# Titan_Balancer_1.net
KiCad netlist of a schematic drawn in Altium Designer
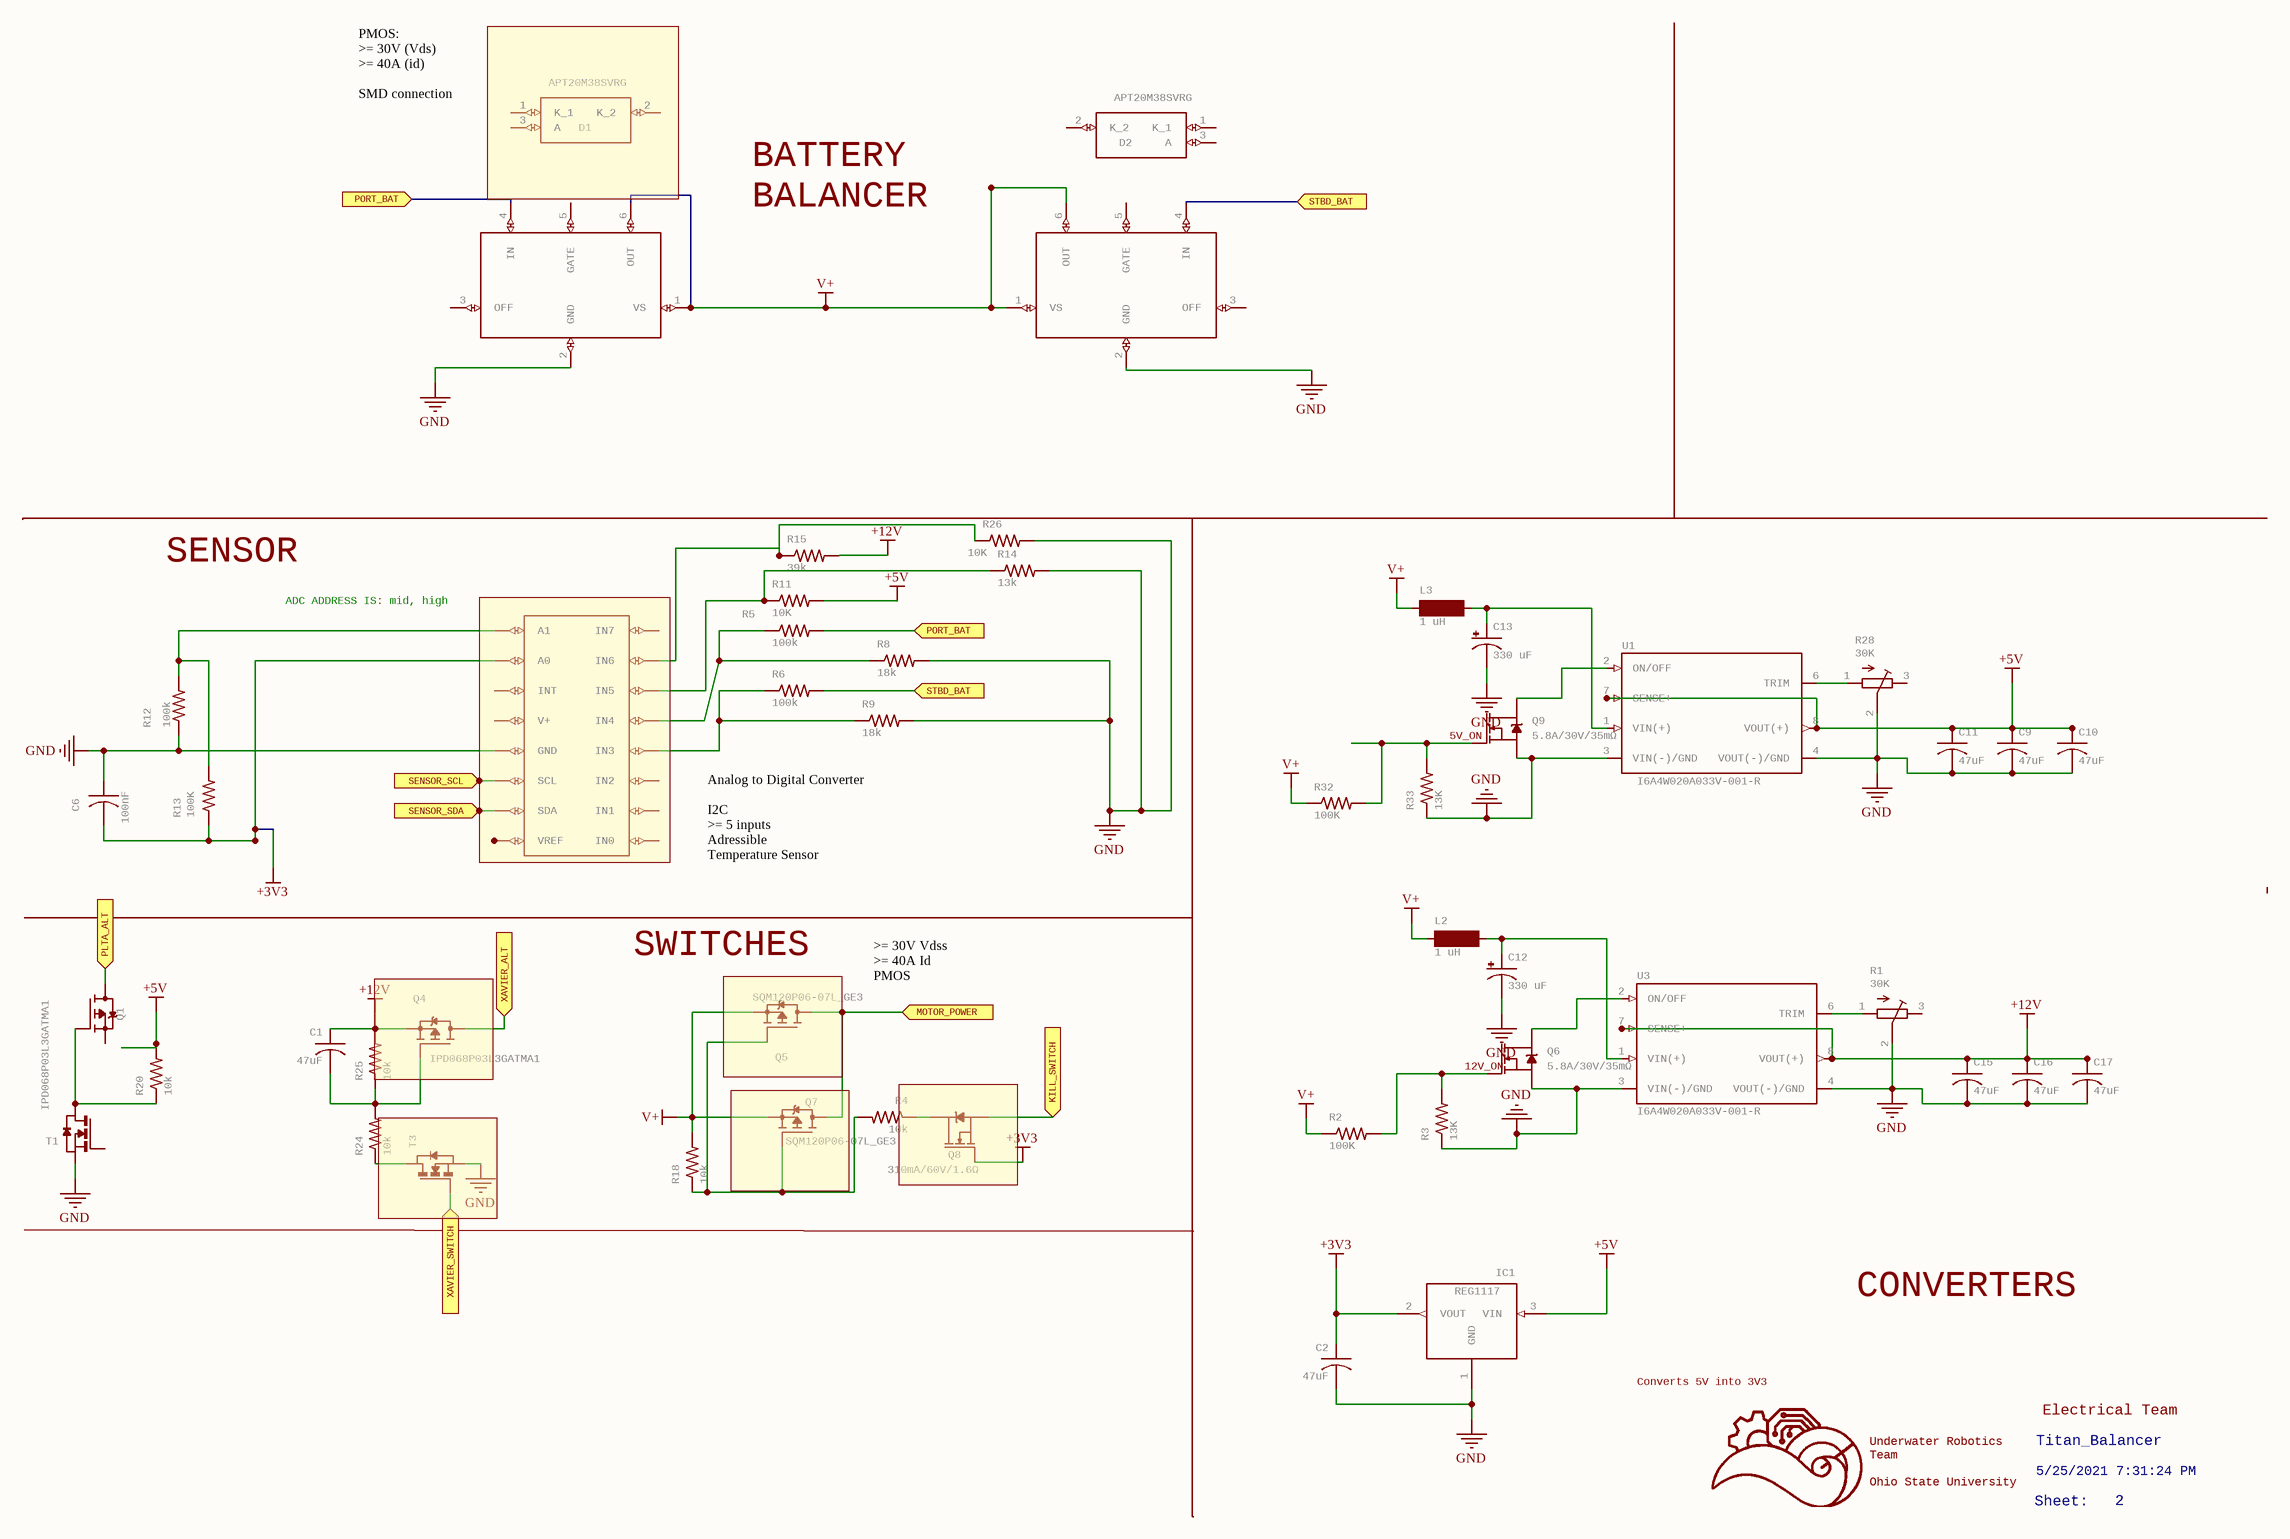
[diagram p0: Titan_Balancer_1.SchDoc]

(export (version "E")
  (design (tool "Eeschema 10.0.6"))
  (components
    (comp (ref "C1")
      (value "47uF")
      (footprint "C0603")
      (description "CAPACITOR, American symbol")
      (libsource (lib "rcl") (part "C-USC0603"))
    )
    (comp (ref "C2")
      (value "47uF")
      (footprint "C0603")
      (description "CAPACITOR, American symbol")
      (libsource (lib "") (part "C-USC0603_1"))
    )
    (comp (ref "C6")
      (value "100nF")
      (footprint "C0603")
      (description "CAPACITOR, American symbol")
      (libsource (lib "rcl") (part "C-USC0603"))
    )
    (comp (ref "C9")
      (value "47uF")
      (footprint "C0603")
      (description "CAPACITOR, American symbol")
      (libsource (lib "rcl") (part "C-USC0603"))
    )
    (comp (ref "C10")
      (value "47uF")
      (footprint "C0603")
      (description "CAPACITOR, American symbol")
      (libsource (lib "rcl") (part "C-USC0603"))
    )
    (comp (ref "C11")
      (value "47uF")
      (footprint "C0603")
      (description "CAPACITOR, American symbol")
      (libsource (lib "rcl") (part "C-USC0603"))
    )
    (comp (ref "C12")
      (value "330 uF")
      (footprint "153CLV-0810")
      (description "POLARIZED CAPACITOR, American symbol")
      (libsource (lib "rcl") (part "CPOL-US153CLV-0810"))
    )
    (comp (ref "C13")
      (value "330 uF")
      (footprint "153CLV-0810")
      (description "POLARIZED CAPACITOR, American symbol")
      (libsource (lib "rcl") (part "CPOL-US153CLV-0810"))
    )
    (comp (ref "C15")
      (value "47uF")
      (footprint "C0603")
      (description "CAPACITOR, American symbol")
      (libsource (lib "rcl") (part "C-USC0603"))
    )
    (comp (ref "C16")
      (value "47uF")
      (footprint "C0603")
      (description "CAPACITOR, American symbol")
      (libsource (lib "rcl") (part "C-USC0603"))
    )
    (comp (ref "C17")
      (value "47uF")
      (footprint "C0603")
      (description "CAPACITOR, American symbol")
      (libsource (lib "rcl") (part "C-USC0603"))
    )
    (comp (ref "D1")
      (value "APT20M38SVRG")
      (footprint "APT60DQ60SG")
      (description "Rectifiers FG, FRED, 600V, 60A, D3, TO-268, RoHS   Source:  Datasheet")
      (fields
        (field (name "ARROW_PART_NUMBER") "APT60DQ60SG")
        (field (name "MOUSER_PART_NUMBER") "494-APT60DQ60SG")
      )
      (libsource (lib "APT60DQ60SG") (part "APT60DQ60SG"))
    )
    (comp (ref "D2")
      (value "APT20M38SVRG")
      (footprint "APT60DQ60SG")
      (description "Rectifiers FG, FRED, 600V, 60A, D3, TO-268, RoHS   Source:  Datasheet")
      (fields
        (field (name "ARROW_PART_NUMBER") "APT60DQ60SG")
        (field (name "MOUSER_PART_NUMBER") "494-APT60DQ60SG")
      )
      (libsource (lib "APT60DQ60SG") (part "APT60DQ60SG"))
    )
    (comp (ref "IC1")
      (value "REG1117")
      (footprint "SOT223")
      (description "800mA and 1A Low Dropout (LDO) Positive Regulator   1.8V, 2.5V, 2.85V, 3.3V, 5V, and Adj")
      (fields (field (name "MF") "MF") (field (name "LIBRARYNAME") "burr-brown"))
      (libsource (lib "burr-brown") (part "REG1117"))
    )
    (comp (ref "L2")
      (value "1 uH")
      (footprint "MS85")
      (description "INDUCTOR   SMD power inductor")
      (fields
        (field (name "MF") "MF")
        (field (name "MPN") "MPN")
        (field (name "LIBRARYNAME") "inductor-neosid")
      )
      (libsource (lib "inductor-neosid") (part "MS85"))
    )
    (comp (ref "L3")
      (value "1 uH")
      (footprint "MS85")
      (description "INDUCTOR   SMD power inductor")
      (fields
        (field (name "MF") "MF")
        (field (name "MPN") "MPN")
        (field (name "LIBRARYNAME") "inductor-neosid")
      )
      (libsource (lib "inductor-neosid") (part "MS85"))
    )
    (comp (ref "Q1")
      (value "IPD068P03L3GATMA1")
      (footprint "TO252")
      (libsource (lib "transistor-fet") (part "SPD30P06PTO252"))
    )
    (comp (ref "Q4")
      (value "IPD068P03L3GATMA1")
      (footprint "TO252")
      (libsource (lib "transistor-fet") (part "SPD30P06PTO252"))
    )
    (comp (ref "Q5")
      (value "SQM120P06-07L_GE3")
      (footprint "TO263")
      (libsource (lib "transistor-fet") (part "SPB80P06P"))
    )
    (comp (ref "Q6")
      (value "5.8A/30V/35mΩ")
      (footprint "SOT23-3")
      (libsource (lib "SparkFun-DiscreteSemi") (part "MOSFET-NCH-AO3404A"))
    )
    (comp (ref "Q7")
      (value "SQM120P06-07L_GE3")
      (footprint "TO263")
      (libsource (lib "transistor-fet") (part "SPB80P06P"))
    )
    (comp (ref "Q8")
      (value "310mA/60V/1.6Ω")
      (footprint "SOT323")
      (libsource (lib "SparkFun-DiscreteSemi") (part "MOSFET-NCH-2N7002PW"))
    )
    (comp (ref "Q9")
      (value "5.8A/30V/35mΩ")
      (footprint "SOT23-3")
      (libsource (lib "SparkFun-DiscreteSemi") (part "MOSFET-NCH-AO3404A"))
    )
    (comp (ref "R1")
      (value "30K")
      (footprint "RTRIM3103")
      (description "Trimm resistor")
      (libsource (lib "resistor") (part "R-TRIMM3103"))
    )
    (comp (ref "R2")
      (value "100K")
      (footprint "R0603")
      (description "RESISTOR, American symbol")
      (libsource (lib "rcl") (part "R-US_R0603"))
    )
    (comp (ref "R3")
      (value "13K")
      (footprint "R0603")
      (description "RESISTOR, American symbol")
      (libsource (lib "rcl") (part "R-US_R0603"))
    )
    (comp (ref "R4")
      (value "10k")
      (footprint "R0603")
      (description "RESISTOR, American symbol")
      (libsource (lib "rcl") (part "R-US_R0603"))
    )
    (comp (ref "R5")
      (value "100k")
      (footprint "R0603")
      (description "RESISTOR, American symbol")
      (libsource (lib "rcl") (part "R-US_R0603"))
    )
    (comp (ref "R6")
      (value "100k")
      (footprint "R0603")
      (description "RESISTOR, American symbol")
      (libsource (lib "rcl") (part "R-US_R0603"))
    )
    (comp (ref "R8")
      (value "18k")
      (footprint "R0603")
      (description "RESISTOR, American symbol")
      (libsource (lib "rcl") (part "R-US_R0603"))
    )
    (comp (ref "R9")
      (value "18k")
      (footprint "R0603")
      (description "RESISTOR, American symbol")
      (libsource (lib "rcl") (part "R-US_R0603"))
    )
    (comp (ref "R11")
      (value "10K")
      (footprint "R0603")
      (description "RESISTOR, American symbol")
      (libsource (lib "rcl") (part "R-US_R0603"))
    )
    (comp (ref "R12")
      (value "100k")
      (footprint "R0603")
      (description "RESISTOR, American symbol")
      (libsource (lib "rcl") (part "R-US_R0603"))
    )
    (comp (ref "R13")
      (value "100K")
      (footprint "R0603")
      (description "RESISTOR, American symbol")
      (libsource (lib "rcl") (part "R-US_R0603"))
    )
    (comp (ref "R14")
      (value "13k")
      (footprint "R0603")
      (description "RESISTOR, American symbol")
      (libsource (lib "rcl") (part "R-US_R0603"))
    )
    (comp (ref "R15")
      (value "39k")
      (footprint "R0603")
      (description "RESISTOR, American symbol")
      (libsource (lib "rcl") (part "R-US_R0603"))
    )
    (comp (ref "R18")
      (value "10k")
      (footprint "R0603")
      (description "RESISTOR, American symbol")
      (libsource (lib "rcl") (part "R-US_R0603"))
    )
    (comp (ref "R20")
      (value "10k")
      (footprint "R0603")
      (description "RESISTOR, American symbol")
      (libsource (lib "rcl") (part "R-US_R0603"))
    )
    (comp (ref "R24")
      (value "10k")
      (footprint "R0603")
      (description "RESISTOR, American symbol")
      (libsource (lib "rcl") (part "R-US_R0603"))
    )
    (comp (ref "R25")
      (value "10k")
      (footprint "R0603")
      (description "RESISTOR, American symbol")
      (libsource (lib "rcl") (part "R-US_R0603"))
    )
    (comp (ref "R26")
      (value "10K")
      (footprint "R0603")
      (description "RESISTOR, American symbol")
      (libsource (lib "rcl") (part "R-US_R0603"))
    )
    (comp (ref "R28")
      (value "30K")
      (footprint "RTRIM3103")
      (description "Trimm resistor")
      (libsource (lib "resistor") (part "R-TRIMM3103"))
    )
    (comp (ref "R32")
      (value "100K")
      (footprint "R0603")
      (description "RESISTOR, American symbol")
      (libsource (lib "rcl") (part "R-US_R0603"))
    )
    (comp (ref "R33")
      (value "13K")
      (footprint "R0603")
      (description "RESISTOR, American symbol")
      (libsource (lib "rcl") (part "R-US_R0603"))
    )
    (comp (ref "T1")
      (value "NMOSSOT23")
      (footprint "SOT-23")
      (description "MOS FET")
      (fields (field (name "MF") "MF") (field (name "MPN") "MPN"))
      (libsource (lib "") (part "NMOSSOT23_1"))
    )
    (comp (ref "T3")
      (value "NMOSSOT23")
      (footprint "SOT-23")
      (description "MOS FET")
      (fields (field (name "MF") "MF") (field (name "MPN") "MPN"))
      (libsource (lib "zetex") (part "NMOSSOT23"))
    )
    (comp (ref "U$5") (value "LM5050") (footprint "LM5050") (libsource (lib "LM5050") (part "LM5050")))
    (comp (ref "U$6") (value "LM5050") (footprint "LM5050") (libsource (lib "LM5050") (part "LM5050")))
    (comp (ref "U$9")
      (value "ADC128D818")
      (footprint "TSSOP-16")
      (libsource (lib "ADC128D818") (part "ADC128D818"))
    )
    (comp (ref "U1")
      (value "I6A4W020A033V-001-R")
      (footprint "TDK-LAMBDA_I6A4W020A033V-001-R")
      (description "Dc-Dc, Pcb Mount, Sixteenth Brick, Input 24vdc, Output 3.3-15v 20a, 250w, Neg Logic")
      (fields (field (name "DIGI-KEY_PART_NUMBER") "285-2503-ND") (field (name "MF") "TDK-Lambda Americas"))
      (libsource (lib "I6A4W020A033V-001-R") (part "I6A4W020A033V-001-R"))
    )
    (comp (ref "U3")
      (value "I6A4W020A033V-001-R")
      (footprint "TDK-LAMBDA_I6A4W020A033V-001-R")
      (description "Dc-Dc, Pcb Mount, Sixteenth Brick, Input 24vdc, Output 3.3-15v 20a, 250w, Neg Logic")
      (fields (field (name "DIGI-KEY_PART_NUMBER") "285-2503-ND") (field (name "MF") "TDK-Lambda Americas"))
      (libsource (lib "I6A4W020A033V-001-R") (part "I6A4W020A033V-001-R"))
    )
  )
  (nets
    (net (code "1") (name "+3V3") (class "Default")
      (node (ref "C2") (pin "1") (pinfunction "1_1") (pintype "passive"))
      (node (ref "C6") (pin "2") (pinfunction "2_2") (pintype "passive"))
      (node (ref "IC1") (pin "2") (pinfunction "VOUT_2") (pintype "output"))
      (node (ref "Q8") (pin "1") (pinfunction "G_1") (pintype "bidirectional"))
      (node (ref "R13") (pin "1") (pinfunction "1_1") (pintype "passive"))
      (node (ref "U$9") (pin "A0") (pinfunction "A0_A0") (pintype "bidirectional"))
    )
    (net (code "2") (name "+5V") (class "Default")
      (node (ref "C10") (pin "1") (pinfunction "1_1") (pintype "passive"))
      (node (ref "C11") (pin "1") (pinfunction "1_1") (pintype "passive"))
      (node (ref "C9") (pin "1") (pinfunction "1_1") (pintype "passive"))
      (node (ref "IC1") (pin "3") (pinfunction "VIN_3") (pintype "input"))
      (node (ref "R11") (pin "2") (pinfunction "2_2") (pintype "passive"))
      (node (ref "R20") (pin "2") (pinfunction "2_2") (pintype "passive"))
      (node (ref "U1") (pin "7") (pinfunction "SENSE+_7") (pintype "input"))
      (node (ref "U1") (pin "8") (pinfunction "VOUT(+)_8") (pintype "output"))
    )
    (net (code "3") (name "+12V") (class "Default")
      (node (ref "C1") (pin "1") (pinfunction "1_1") (pintype "passive"))
      (node (ref "C15") (pin "1") (pinfunction "1_1") (pintype "passive"))
      (node (ref "C16") (pin "1") (pinfunction "1_1") (pintype "passive"))
      (node (ref "C17") (pin "1") (pinfunction "1_1") (pintype "passive"))
      (node (ref "Q4") (pin "2") (pinfunction "S_2") (pintype "passive"))
      (node (ref "R15") (pin "2") (pinfunction "2_2") (pintype "passive"))
      (node (ref "R25") (pin "2") (pinfunction "2_2") (pintype "passive"))
      (node (ref "U3") (pin "7") (pinfunction "SENSE+_7") (pintype "input"))
      (node (ref "U3") (pin "8") (pinfunction "VOUT(+)_8") (pintype "output"))
    )
    (net (code "4") (name "/5V_ON") (class "Default")
      (node (ref "Q9") (pin "1") (pinfunction "G_1") (pintype "bidirectional"))
      (node (ref "R32") (pin "2") (pinfunction "2_2") (pintype "passive"))
      (node (ref "R33") (pin "2") (pinfunction "2_2") (pintype "passive"))
    )
    (net (code "5") (name "/12V_ON") (class "Default")
      (node (ref "Q6") (pin "1") (pinfunction "G_1") (pintype "bidirectional"))
      (node (ref "R2") (pin "2") (pinfunction "2_2") (pintype "passive"))
      (node (ref "R3") (pin "2") (pinfunction "2_2") (pintype "passive"))
    )
    (net (code "6") (name "/KILL_SWITCH") (class "Default")
      (node (ref "Q8") (pin "2") (pinfunction "S_2") (pintype "bidirectional"))
    )
    (net (code "7") (name "/MOTOR_POWER") (class "Default")
      (node (ref "Q5") (pin "3") (pinfunction "D_3") (pintype "passive"))
      (node (ref "Q7") (pin "3") (pinfunction "D_3") (pintype "passive"))
    )
    (net (code "8") (name "/PLTA_ALT") (class "Default")
      (node (ref "Q1") (pin "3") (pinfunction "D_3") (pintype "passive"))
    )
    (net (code "9") (name "/PORT_BAT") (class "Default")
      (node (ref "R5") (pin "2") (pinfunction "2_2") (pintype "passive"))
      (node (ref "U$5") (pin "4") (pinfunction "IN_4") (pintype "bidirectional"))
    )
    (net (code "10") (name "/SENSOR_SCL") (class "Default")
      (node (ref "U$9") (pin "SCL") (pinfunction "SCL_SCL") (pintype "bidirectional"))
    )
    (net (code "11") (name "/SENSOR_SDA") (class "Default")
      (node (ref "U$9") (pin "SDA") (pinfunction "SDA_SDA") (pintype "bidirectional"))
    )
    (net (code "12") (name "/STBD_BAT") (class "Default")
      (node (ref "R6") (pin "2") (pinfunction "2_2") (pintype "passive"))
      (node (ref "U$6") (pin "4") (pinfunction "IN_4") (pintype "bidirectional"))
    )
    (net (code "13") (name "/XAVIER_ALT") (class "Default")
      (node (ref "Q4") (pin "3") (pinfunction "D_3") (pintype "passive"))
    )
    (net (code "14") (name "/XAVIER_SWITCH") (class "Default")
      (node (ref "T3") (pin "3") (pinfunction "G_3") (pintype "passive"))
    )
    (net (code "15") (name "GND") (class "Default")
      (node (ref "C10") (pin "2") (pinfunction "2_2") (pintype "passive"))
      (node (ref "C11") (pin "2") (pinfunction "2_2") (pintype "passive"))
      (node (ref "C12") (pin "-") (pinfunction "-_-") (pintype "passive"))
      (node (ref "C13") (pin "-") (pinfunction "-_-") (pintype "passive"))
      (node (ref "C15") (pin "2") (pinfunction "2_2") (pintype "passive"))
      (node (ref "C16") (pin "2") (pinfunction "2_2") (pintype "passive"))
      (node (ref "C17") (pin "2") (pinfunction "2_2") (pintype "passive"))
      (node (ref "C2") (pin "2") (pinfunction "2_2") (pintype "passive"))
      (node (ref "C6") (pin "1") (pinfunction "1_1") (pintype "passive"))
      (node (ref "C9") (pin "2") (pinfunction "2_2") (pintype "passive"))
      (node (ref "IC1") (pin "1") (pinfunction "GND_1") (pintype "power_in"))
      (node (ref "Q6") (pin "2") (pinfunction "S_2") (pintype "bidirectional"))
      (node (ref "Q9") (pin "2") (pinfunction "S_2") (pintype "bidirectional"))
      (node (ref "R1") (pin "2") (pinfunction "S_2") (pintype "passive"))
      (node (ref "R12") (pin "1") (pinfunction "1_1") (pintype "passive"))
      (node (ref "R14") (pin "2") (pinfunction "2_2") (pintype "passive"))
      (node (ref "R26") (pin "2") (pinfunction "2_2") (pintype "passive"))
      (node (ref "R28") (pin "2") (pinfunction "S_2") (pintype "passive"))
      (node (ref "R3") (pin "1") (pinfunction "1_1") (pintype "passive"))
      (node (ref "R33") (pin "1") (pinfunction "1_1") (pintype "passive"))
      (node (ref "R8") (pin "2") (pinfunction "2_2") (pintype "passive"))
      (node (ref "R9") (pin "2") (pinfunction "2_2") (pintype "passive"))
      (node (ref "T1") (pin "2") (pinfunction "S_2") (pintype "passive"))
      (node (ref "T3") (pin "2") (pinfunction "S_2") (pintype "passive"))
      (node (ref "U$5") (pin "2") (pinfunction "GND_2") (pintype "bidirectional"))
      (node (ref "U$6") (pin "2") (pinfunction "GND_2") (pintype "bidirectional"))
      (node (ref "U$9") (pin "GND") (pinfunction "GND_GND") (pintype "bidirectional"))
      (node (ref "U1") (pin "3") (pinfunction "VIN(-)/GND_3") (pintype "power_in"))
      (node (ref "U1") (pin "4") (pinfunction "VOUT(-)/GND_4") (pintype "power_in"))
      (node (ref "U3") (pin "3") (pinfunction "VIN(-)/GND_3") (pintype "power_in"))
      (node (ref "U3") (pin "4") (pinfunction "VOUT(-)/GND_4") (pintype "power_in"))
    )
    (net (code "16") (name "Net-(Q1-G)") (class "Default")
      (node (ref "Q1") (pin "1") (pinfunction "G_1") (pintype "passive"))
      (node (ref "R20") (pin "1") (pinfunction "1_1") (pintype "passive"))
      (node (ref "T1") (pin "1") (pinfunction "D_1") (pintype "passive"))
    )
    (net (code "17") (name "Net-(Q4-G)") (class "Default")
      (node (ref "C1") (pin "2") (pinfunction "2_2") (pintype "passive"))
      (node (ref "Q4") (pin "1") (pinfunction "G_1") (pintype "passive"))
      (node (ref "R24") (pin "2") (pinfunction "2_2") (pintype "passive"))
      (node (ref "R25") (pin "1") (pinfunction "1_1") (pintype "passive"))
    )
    (net (code "18") (name "Net-(Q5-G)") (class "Default")
      (node (ref "Q5") (pin "1") (pinfunction "G_1") (pintype "passive"))
      (node (ref "Q7") (pin "1") (pinfunction "G_1") (pintype "passive"))
      (node (ref "R18") (pin "1") (pinfunction "1_1") (pintype "passive"))
      (node (ref "R4") (pin "2") (pinfunction "2_2") (pintype "passive"))
    )
    (net (code "19") (name "Net-(Q6-D)") (class "Default")
      (node (ref "Q6") (pin "3") (pinfunction "D_3") (pintype "bidirectional"))
      (node (ref "U3") (pin "2") (pinfunction "ON/OFF_2") (pintype "input"))
    )
    (net (code "20") (name "Net-(Q8-D)") (class "Default")
      (node (ref "Q8") (pin "3") (pinfunction "D_3") (pintype "bidirectional"))
      (node (ref "R4") (pin "1") (pinfunction "1_1") (pintype "passive"))
    )
    (net (code "21") (name "Net-(Q9-D)") (class "Default")
      (node (ref "Q9") (pin "3") (pinfunction "D_3") (pintype "bidirectional"))
      (node (ref "U1") (pin "2") (pinfunction "ON/OFF_2") (pintype "input"))
    )
    (net (code "22") (name "Net-(R1-A)") (class "Default")
      (node (ref "R1") (pin "1") (pinfunction "A_1") (pintype "passive"))
      (node (ref "U3") (pin "6") (pinfunction "TRIM_6") (pintype "passive"))
    )
    (net (code "23") (name "Net-(R5-Pad1)") (class "Default")
      (node (ref "R5") (pin "1") (pinfunction "1_1") (pintype "passive"))
      (node (ref "R8") (pin "1") (pinfunction "1_1") (pintype "passive"))
      (node (ref "U$9") (pin "IN4") (pinfunction "IN4_IN4") (pintype "bidirectional"))
    )
    (net (code "24") (name "Net-(R6-Pad1)") (class "Default")
      (node (ref "R6") (pin "1") (pinfunction "1_1") (pintype "passive"))
      (node (ref "R9") (pin "1") (pinfunction "1_1") (pintype "passive"))
      (node (ref "U$9") (pin "IN3") (pinfunction "IN3_IN3") (pintype "bidirectional"))
    )
    (net (code "25") (name "Net-(R11-Pad1)") (class "Default")
      (node (ref "R11") (pin "1") (pinfunction "1_1") (pintype "passive"))
      (node (ref "R14") (pin "1") (pinfunction "1_1") (pintype "passive"))
      (node (ref "U$9") (pin "IN5") (pinfunction "IN5_IN5") (pintype "bidirectional"))
    )
    (net (code "26") (name "Net-(R12-Pad2)") (class "Default")
      (node (ref "R12") (pin "2") (pinfunction "2_2") (pintype "passive"))
      (node (ref "R13") (pin "2") (pinfunction "2_2") (pintype "passive"))
      (node (ref "U$9") (pin "A1") (pinfunction "A1_A1") (pintype "bidirectional"))
    )
    (net (code "27") (name "Net-(R15-Pad1)") (class "Default")
      (node (ref "R15") (pin "1") (pinfunction "1_1") (pintype "passive"))
      (node (ref "R26") (pin "1") (pinfunction "1_1") (pintype "passive"))
      (node (ref "U$9") (pin "IN6") (pinfunction "IN6_IN6") (pintype "bidirectional"))
    )
    (net (code "28") (name "Net-(R28-A)") (class "Default")
      (node (ref "R28") (pin "1") (pinfunction "A_1") (pintype "passive"))
      (node (ref "U1") (pin "6") (pinfunction "TRIM_6") (pintype "passive"))
    )
    (net (code "29") (name "Net-(T3-D)") (class "Default")
      (node (ref "R24") (pin "1") (pinfunction "1_1") (pintype "passive"))
      (node (ref "T3") (pin "1") (pinfunction "D_1") (pintype "passive"))
    )
    (net (code "30") (name "Net-(U1-VIN(+))") (class "Default")
      (node (ref "C13") (pin "+") (pinfunction "+_+") (pintype "passive"))
      (node (ref "L3") (pin "2") (pinfunction "2_2") (pintype "passive"))
      (node (ref "U1") (pin "1") (pinfunction "VIN(+)_1") (pintype "input"))
    )
    (net (code "31") (name "Net-(U3-VIN(+))") (class "Default")
      (node (ref "C12") (pin "+") (pinfunction "+_+") (pintype "passive"))
      (node (ref "L2") (pin "2") (pinfunction "2_2") (pintype "passive"))
      (node (ref "U3") (pin "1") (pinfunction "VIN(+)_1") (pintype "input"))
    )
    (net (code "32") (name "V+") (class "Default")
      (node (ref "L2") (pin "1") (pinfunction "1_1") (pintype "passive"))
      (node (ref "L3") (pin "1") (pinfunction "1_1") (pintype "passive"))
      (node (ref "Q5") (pin "2") (pinfunction "S_2") (pintype "passive"))
      (node (ref "Q7") (pin "2") (pinfunction "S_2") (pintype "passive"))
      (node (ref "R18") (pin "2") (pinfunction "2_2") (pintype "passive"))
      (node (ref "R2") (pin "1") (pinfunction "1_1") (pintype "passive"))
      (node (ref "R32") (pin "1") (pinfunction "1_1") (pintype "passive"))
      (node (ref "U$5") (pin "1") (pinfunction "VS_1") (pintype "bidirectional"))
      (node (ref "U$5") (pin "6") (pinfunction "OUT_6") (pintype "bidirectional"))
      (node (ref "U$6") (pin "1") (pinfunction "VS_1") (pintype "bidirectional"))
      (node (ref "U$6") (pin "6") (pinfunction "OUT_6") (pintype "bidirectional"))
    )
    (net (code "33") (name "unconnected-(D1-A-Pad3)") (class "Default")
      (node (ref "D1") (pin "3") (pinfunction "A_3") (pintype "bidirectional"))
    )
    (net (code "34") (name "unconnected-(D1-K_1-Pad1)") (class "Default")
      (node (ref "D1") (pin "1") (pinfunction "K_1_1") (pintype "bidirectional"))
    )
    (net (code "35") (name "unconnected-(D1-K_2-Pad2)") (class "Default")
      (node (ref "D1") (pin "2") (pinfunction "K_2_2") (pintype "bidirectional"))
    )
    (net (code "36") (name "unconnected-(D2-A-Pad3)") (class "Default")
      (node (ref "D2") (pin "3") (pinfunction "A_3") (pintype "bidirectional"))
    )
    (net (code "37") (name "unconnected-(D2-K_1-Pad1)") (class "Default")
      (node (ref "D2") (pin "1") (pinfunction "K_1_1") (pintype "bidirectional"))
    )
    (net (code "38") (name "unconnected-(D2-K_2-Pad2)") (class "Default")
      (node (ref "D2") (pin "2") (pinfunction "K_2_2") (pintype "bidirectional"))
    )
    (net (code "39") (name "unconnected-(Q1-S-Pad2)") (class "Default")
      (node (ref "Q1") (pin "2") (pinfunction "S_2") (pintype "passive"))
    )
    (net (code "40") (name "unconnected-(R1-E-Pad3)") (class "Default")
      (node (ref "R1") (pin "3") (pinfunction "E_3") (pintype "passive"))
    )
    (net (code "41") (name "unconnected-(R28-E-Pad3)") (class "Default")
      (node (ref "R28") (pin "3") (pinfunction "E_3") (pintype "passive"))
    )
    (net (code "42") (name "unconnected-(T1-G-Pad3)") (class "Default")
      (node (ref "T1") (pin "3") (pinfunction "G_3") (pintype "passive"))
    )
    (net (code "43") (name "unconnected-(U$5-GATE-Pad5)") (class "Default")
      (node (ref "U$5") (pin "5") (pinfunction "GATE_5") (pintype "bidirectional"))
    )
    (net (code "44") (name "unconnected-(U$5-OFF-Pad3)") (class "Default")
      (node (ref "U$5") (pin "3") (pinfunction "OFF_3") (pintype "bidirectional"))
    )
    (net (code "45") (name "unconnected-(U$6-GATE-Pad5)") (class "Default")
      (node (ref "U$6") (pin "5") (pinfunction "GATE_5") (pintype "bidirectional"))
    )
    (net (code "46") (name "unconnected-(U$6-OFF-Pad3)") (class "Default")
      (node (ref "U$6") (pin "3") (pinfunction "OFF_3") (pintype "bidirectional"))
    )
    (net (code "47") (name "unconnected-(U$9-PadIN0)") (class "Default")
      (node (ref "U$9") (pin "IN0") (pinfunction "IN0_IN0") (pintype "bidirectional"))
    )
    (net (code "48") (name "unconnected-(U$9-PadIN1)") (class "Default")
      (node (ref "U$9") (pin "IN1") (pinfunction "IN1_IN1") (pintype "bidirectional"))
    )
    (net (code "49") (name "unconnected-(U$9-PadIN2)") (class "Default")
      (node (ref "U$9") (pin "IN2") (pinfunction "IN2_IN2") (pintype "bidirectional"))
    )
    (net (code "50") (name "unconnected-(U$9-PadIN7)") (class "Default")
      (node (ref "U$9") (pin "IN7") (pinfunction "IN7_IN7") (pintype "bidirectional"))
    )
    (net (code "51") (name "unconnected-(U$9-PadINT)") (class "Default")
      (node (ref "U$9") (pin "INT") (pinfunction "INT_INT") (pintype "bidirectional"))
    )
    (net (code "52") (name "unconnected-(U$9-PadV+)") (class "Default")
      (node (ref "U$9") (pin "V+") (pinfunction "V+_V+") (pintype "bidirectional"))
    )
    (net (code "53") (name "unconnected-(U$9-PadVREF)") (class "Default")
      (node (ref "U$9") (pin "VREF") (pinfunction "VREF_VREF") (pintype "bidirectional"))
    )
  )
)
